# MOSFET.net
KiCad netlist of a schematic drawn in Altium Designer
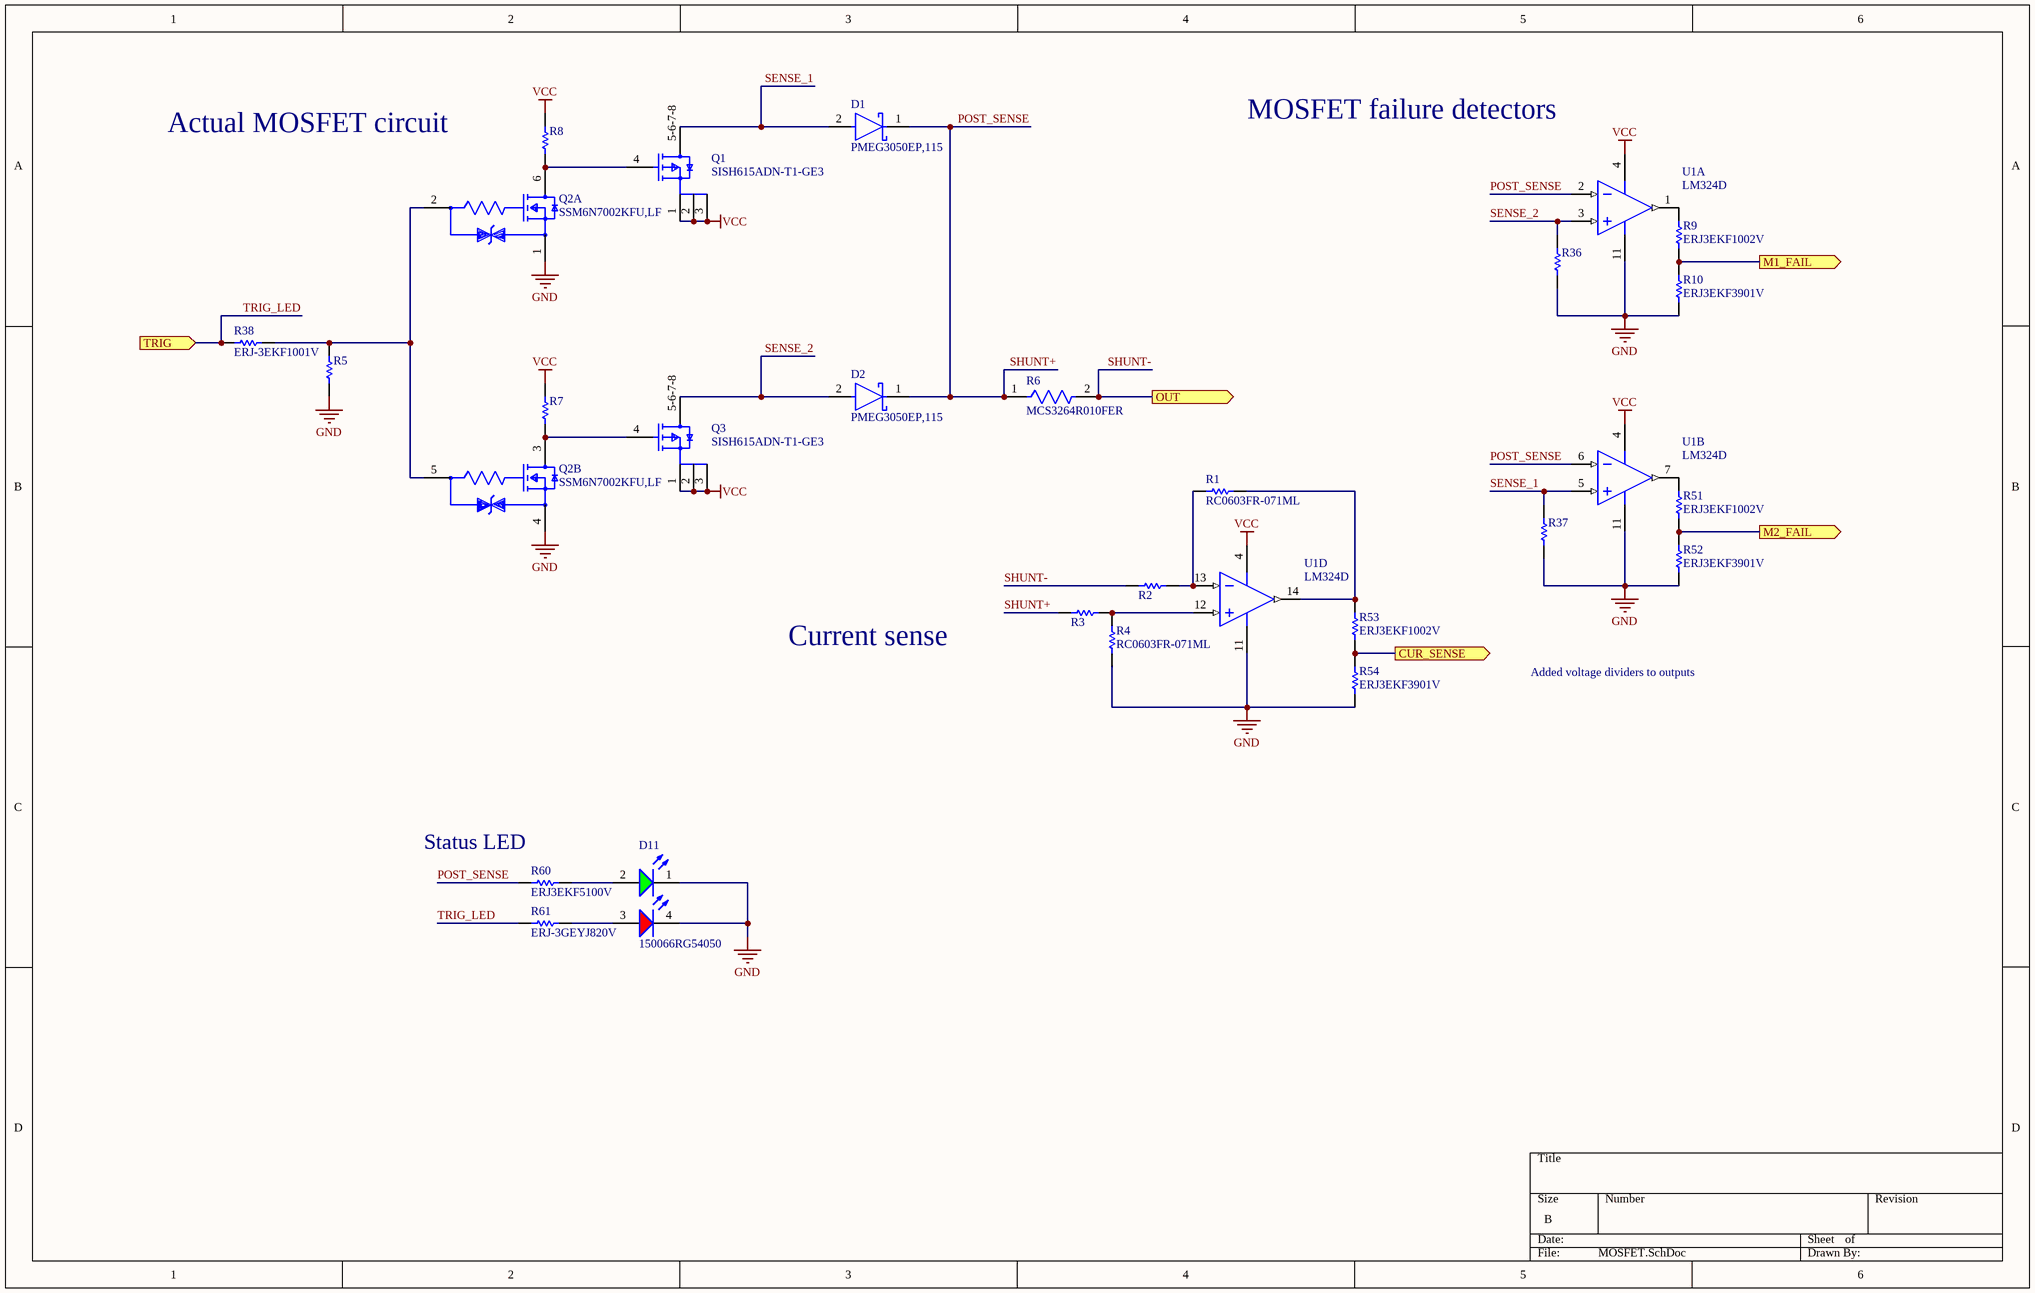
[diagram p0: MOSFET.SchDoc]

(export (version "E")
  (design (tool "Eeschema 10.0.6"))
  (components
    (comp (ref "D1")
      (value "PMEG3050EP,115")
      (footprint "FP-SOD128-MFG")
      (description "DIODE SCHOTTKY 30V 5A SOD128")
      (libsource (lib "Altium Content Vault") (part "1d6ec82d83fb6aee721767c19dac4b9"))
    )
    (comp (ref "D2")
      (value "PMEG3050EP,115")
      (footprint "FP-SOD128-MFG")
      (description "DIODE SCHOTTKY 30V 5A SOD128")
      (libsource (lib "Altium Content Vault") (part "1d6ec82d83fb6aee721767c19dac4b9"))
    )
    (comp (ref "D11")
      (value "150066RG54050")
      (footprint "WL-SBCD_0606")
      (description "Led, Red/Grn, 180Mcd/230Mcd, 624Nm/525Nm Rohs Compliant: Yes")
      (libsource (lib "uORocketry Hardware") (part "WL-SBCD_0606_Red & Green"))
    )
    (comp (ref "Q1")
      (value "SISH615ADN-T1-GE3")
      (footprint "SISH615ADN-T1-GE3-Footprint-1")
      (description "Trans MOSFET P-CH 20V 22.1A 8-Pin PowerPAK 1212 EP T/R")
      (libsource (lib "uORocketry Hardware") (part "SISH615ADN-T1-GE3-Symbol-1"))
    )
    (comp (ref "Q2")
      (value "SSM6N7002KFU,LF")
      (footprint "FP-SSOP6-P-0_65A-MFG")
      (description "MOSFET 2N-CH 60V 0.3A")
      (libsource (lib "Altium Content Vault") (part "088aa6ac103fdeebe0d1c52ece6b7b9"))
    )
    (comp (ref "Q3")
      (value "SISH615ADN-T1-GE3")
      (footprint "SISH615ADN-T1-GE3-Footprint-1")
      (description "Trans MOSFET P-CH 20V 22.1A 8-Pin PowerPAK 1212 EP T/R")
      (libsource (lib "uORocketry Hardware") (part "SISH615ADN-T1-GE3-Symbol-1"))
    )
    (comp (ref "R1")
      (value "RC0603FR-071ML")
      (footprint "RESC1608X55X25LL10T15")
      (description "Chip Resistor, 1 MOhm, +/- 1%, 100 mW, -55 to 155 degC, 0603 (1608 Metric), RoHS, Tape and Reel")
      (fields (field (name "TOLERANCE") "20%"))
      (libsource (lib "Altium Content Vault") (part "RES-2"))
    )
    (comp (ref "R2")
      (value "ERJ3EKF1002V")
      (footprint "RESC1609X55X30LL15T15")
      (description "Chip Resistor, 10 KOhm, +/- 1%, 0.1 W, -55 to 155 degC, 0603 (1608 Metric), RoHS, Tape and Reel")
      (fields (field (name "TOLERANCE") "1%") (field (name "MANUFACTURER") "Panasonic"))
      (libsource (lib "Altium Content Vault") (part "RES-2"))
    )
    (comp (ref "R3")
      (value "ERJ3EKF1002V")
      (footprint "RESC1609X55X30LL15T15")
      (description "Chip Resistor, 10 KOhm, +/- 1%, 0.1 W, -55 to 155 degC, 0603 (1608 Metric), RoHS, Tape and Reel")
      (fields (field (name "TOLERANCE") "1%") (field (name "MANUFACTURER") "Panasonic"))
      (libsource (lib "Altium Content Vault") (part "RES-2"))
    )
    (comp (ref "R4")
      (value "RC0603FR-071ML")
      (footprint "RESC1608X55X25LL10T15")
      (description "Chip Resistor, 1 MOhm, +/- 1%, 100 mW, -55 to 155 degC, 0603 (1608 Metric), RoHS, Tape and Reel")
      (fields (field (name "TOLERANCE") "20%"))
      (libsource (lib "Altium Content Vault") (part "RES-2"))
    )
    (comp (ref "R5")
      (value "ERJ3EKF1002V")
      (footprint "RESC1609X55X30LL15T15")
      (description "Chip Resistor, 10 KOhm, +/- 1%, 0.1 W, -55 to 155 degC, 0603 (1608 Metric), RoHS, Tape and Reel")
      (fields (field (name "TOLERANCE") "1%") (field (name "MANUFACTURER") "Panasonic"))
      (libsource (lib "Altium Content Vault") (part "RES-2"))
    )
    (comp (ref "R6")
      (value "MCS3264R010FER")
      (footprint "FP-MCS3264-MFG")
      (description "RES SMD 10 MOHM 1% 2W 3264")
      (fields (field (name "TOLERANCE") "1%"))
      (libsource (lib "Altium Content Vault") (part "1029c3af85768c4190bb7ad29bc67b5"))
    )
    (comp (ref "R7")
      (value "ERJ3EKF1002V")
      (footprint "RESC1609X55X30LL15T15")
      (description "Chip Resistor, 10 KOhm, +/- 1%, 0.1 W, -55 to 155 degC, 0603 (1608 Metric), RoHS, Tape and Reel")
      (fields (field (name "TOLERANCE") "1%") (field (name "MANUFACTURER") "Panasonic"))
      (libsource (lib "Altium Content Vault") (part "RES-2"))
    )
    (comp (ref "R8")
      (value "ERJ3EKF1002V")
      (footprint "RESC1609X55X30LL15T15")
      (description "Chip Resistor, 10 KOhm, +/- 1%, 0.1 W, -55 to 155 degC, 0603 (1608 Metric), RoHS, Tape and Reel")
      (fields (field (name "TOLERANCE") "1%") (field (name "MANUFACTURER") "Panasonic"))
      (libsource (lib "Altium Content Vault") (part "RES-2"))
    )
    (comp (ref "R9")
      (value "ERJ3EKF1002V")
      (footprint "RESC1609X55X30LL15T15")
      (description "Chip Resistor, 10 KOhm, +/- 1%, 0.1 W, -55 to 155 degC, 0603 (1608 Metric), RoHS, Tape and Reel")
      (fields (field (name "TOLERANCE") "1%") (field (name "MANUFACTURER") "Panasonic"))
      (libsource (lib "Altium Content Vault") (part "RES-2"))
    )
    (comp (ref "R10")
      (value "ERJ3EKF3901V")
      (footprint "RESC1608X55X30ML15T15")
      (fields (field (name "MANUFACTURER") "Panasonic"))
      (libsource (lib "Altium Content Vault") (part "RES"))
    )
    (comp (ref "R36")
      (value "ERJ-3EKF1003V")
      (footprint "RESC1608X55X30ML15T15")
      (fields (field (name "MANUFACTURER") "Panasonic"))
      (libsource (lib "Altium Content Vault") (part "RES"))
    )
    (comp (ref "R37")
      (value "ERJ-3EKF1003V")
      (footprint "RESC1608X55X30ML15T15")
      (fields (field (name "MANUFACTURER") "Panasonic"))
      (libsource (lib "Altium Content Vault") (part "RES"))
    )
    (comp (ref "R38")
      (value "ERJ-3EKF1001V")
      (footprint "RESC1608X55X30LL15T15")
      (fields (field (name "MANUFACTURER") "Panasonic"))
      (libsource (lib "Altium Content Vault") (part "RES"))
    )
    (comp (ref "R51")
      (value "ERJ3EKF1002V")
      (footprint "RESC1609X55X30LL15T15")
      (description "Chip Resistor, 10 KOhm, +/- 1%, 0.1 W, -55 to 155 degC, 0603 (1608 Metric), RoHS, Tape and Reel")
      (fields (field (name "TOLERANCE") "1%") (field (name "MANUFACTURER") "Panasonic"))
      (libsource (lib "Altium Content Vault") (part "RES-2"))
    )
    (comp (ref "R52")
      (value "ERJ3EKF3901V")
      (footprint "RESC1608X55X30ML15T15")
      (fields (field (name "MANUFACTURER") "Panasonic"))
      (libsource (lib "Altium Content Vault") (part "RES"))
    )
    (comp (ref "R53")
      (value "ERJ3EKF1002V")
      (footprint "RESC1609X55X30LL15T15")
      (description "Chip Resistor, 10 KOhm, +/- 1%, 0.1 W, -55 to 155 degC, 0603 (1608 Metric), RoHS, Tape and Reel")
      (fields (field (name "TOLERANCE") "1%") (field (name "MANUFACTURER") "Panasonic"))
      (libsource (lib "Altium Content Vault") (part "RES-2"))
    )
    (comp (ref "R54")
      (value "ERJ3EKF3901V")
      (footprint "RESC1608X55X30ML15T15")
      (fields (field (name "MANUFACTURER") "Panasonic"))
      (libsource (lib "Altium Content Vault") (part "RES"))
    )
    (comp (ref "R60")
      (value "ERJ3EKF5100V")
      (footprint "RESC1608X55X30NL15T15")
      (fields (field (name "MANUFACTURER") "Panasonic"))
      (libsource (lib "Altium Content Vault") (part "RES"))
    )
    (comp (ref "R61")
      (value "ERJ-3GEYJ820V")
      (footprint "RESC1608X55X30NL15T15")
      (fields (field (name "MANUFACTURER") "Panasonic"))
      (libsource (lib "Altium Content Vault") (part "RES"))
    )
    (comp (ref "U1")
      (value "LM324D")
      (footprint "D0014A_L")
      (fields (field (name "MANUFACTURER") "Texas Instruments"))
      (libsource (lib "Altium Content Vault") (part "TI-LMX24_2902X-X14"))
    )
  )
  (nets
    (net (code "1") (name "/CUR_SENSE") (class "Default")
      (node (ref "R53") (pin "1") (pinfunction "1_1") (pintype "passive"))
      (node (ref "R54") (pin "2") (pinfunction "2_2") (pintype "passive"))
    )
    (net (code "2") (name "/M1_FAIL") (class "Default")
      (node (ref "R10") (pin "2") (pinfunction "2_2") (pintype "passive"))
      (node (ref "R9") (pin "1") (pinfunction "1_1") (pintype "passive"))
    )
    (net (code "3") (name "/M2_FAIL") (class "Default")
      (node (ref "R51") (pin "1") (pinfunction "1_1") (pintype "passive"))
      (node (ref "R52") (pin "2") (pinfunction "2_2") (pintype "passive"))
    )
    (net (code "4") (name "/POST_SENSE") (class "Default")
      (node (ref "D1") (pin "1") (pinfunction "C_1") (pintype "passive"))
      (node (ref "D2") (pin "1") (pinfunction "C_1") (pintype "passive"))
      (node (ref "R3") (pin "2") (pinfunction "2_2") (pintype "passive"))
      (node (ref "R6") (pin "1") (pinfunction "1_1") (pintype "passive"))
      (node (ref "R60") (pin "1") (pinfunction "1_1") (pintype "passive"))
      (node (ref "U1") (pin "2") (pinfunction "1IN-_2") (pintype "input"))
      (node (ref "U1") (pin "6") (pinfunction "2IN-_6") (pintype "input"))
    )
    (net (code "5") (name "/SENSE_1") (class "Default")
      (node (ref "D1") (pin "2") (pinfunction "A_2") (pintype "passive"))
      (node (ref "Q1") (pin "5-6-7-8") (pinfunction "D_5-6-7-8") (pintype "passive"))
      (node (ref "R37") (pin "2") (pinfunction "2_2") (pintype "passive"))
      (node (ref "U1") (pin "5") (pinfunction "2IN+_5") (pintype "input"))
    )
    (net (code "6") (name "/SENSE_2") (class "Default")
      (node (ref "D2") (pin "2") (pinfunction "A_2") (pintype "passive"))
      (node (ref "Q3") (pin "5-6-7-8") (pinfunction "D_5-6-7-8") (pintype "passive"))
      (node (ref "R36") (pin "2") (pinfunction "2_2") (pintype "passive"))
      (node (ref "U1") (pin "3") (pinfunction "1IN+_3") (pintype "input"))
    )
    (net (code "7") (name "/SHUNT-") (class "Default")
      (node (ref "R2") (pin "2") (pinfunction "2_2") (pintype "passive"))
      (node (ref "R6") (pin "2") (pinfunction "2_2") (pintype "passive"))
    )
    (net (code "8") (name "/TRIG_LED") (class "Default")
      (node (ref "R38") (pin "1") (pinfunction "1_1") (pintype "passive"))
      (node (ref "R61") (pin "1") (pinfunction "1_1") (pintype "passive"))
    )
    (net (code "9") (name "GND") (class "Default")
      (node (ref "D11") (pin "1") (pinfunction "K_1") (pintype "passive"))
      (node (ref "D11") (pin "4") (pinfunction "K_4") (pintype "passive"))
      (node (ref "Q2") (pin "1") (pinfunction "Source1_1") (pintype "passive"))
      (node (ref "Q2") (pin "4") (pinfunction "Source2_4") (pintype "passive"))
      (node (ref "R10") (pin "1") (pinfunction "1_1") (pintype "passive"))
      (node (ref "R36") (pin "1") (pinfunction "1_1") (pintype "passive"))
      (node (ref "R37") (pin "1") (pinfunction "1_1") (pintype "passive"))
      (node (ref "R4") (pin "1") (pinfunction "1_1") (pintype "passive"))
      (node (ref "R5") (pin "1") (pinfunction "1_1") (pintype "passive"))
      (node (ref "R52") (pin "1") (pinfunction "1_1") (pintype "passive"))
      (node (ref "R54") (pin "1") (pinfunction "1_1") (pintype "passive"))
      (node (ref "U1") (pin "11") (pinfunction "GND_11") (pintype "power_in"))
    )
    (net (code "10") (name "Net-(D11-A-Pad2)") (class "Default")
      (node (ref "D11") (pin "2") (pinfunction "A_2") (pintype "passive"))
      (node (ref "R60") (pin "2") (pinfunction "2_2") (pintype "passive"))
    )
    (net (code "11") (name "Net-(D11-A-Pad3)") (class "Default")
      (node (ref "D11") (pin "3") (pinfunction "A_3") (pintype "passive"))
      (node (ref "R61") (pin "2") (pinfunction "2_2") (pintype "passive"))
    )
    (net (code "12") (name "Net-(Q1-G)") (class "Default")
      (node (ref "Q1") (pin "4") (pinfunction "G_4") (pintype "passive"))
      (node (ref "Q2") (pin "6") (pinfunction "Drain1_6") (pintype "passive"))
      (node (ref "R8") (pin "1") (pinfunction "1_1") (pintype "passive"))
    )
    (net (code "13") (name "Net-(Q2A-Gate1)") (class "Default")
      (node (ref "Q2") (pin "2") (pinfunction "Gate1_2") (pintype "passive"))
      (node (ref "Q2") (pin "5") (pinfunction "Gate2_5") (pintype "passive"))
      (node (ref "R38") (pin "2") (pinfunction "2_2") (pintype "passive"))
      (node (ref "R5") (pin "2") (pinfunction "2_2") (pintype "passive"))
    )
    (net (code "14") (name "Net-(Q2B-Drain2)") (class "Default")
      (node (ref "Q2") (pin "3") (pinfunction "Drain2_3") (pintype "passive"))
      (node (ref "Q3") (pin "4") (pinfunction "G_4") (pintype "passive"))
      (node (ref "R7") (pin "1") (pinfunction "1_1") (pintype "passive"))
    )
    (net (code "15") (name "Net-(U1A-1OUT)") (class "Default")
      (node (ref "R9") (pin "2") (pinfunction "2_2") (pintype "passive"))
      (node (ref "U1") (pin "1") (pinfunction "1OUT_1") (pintype "output"))
    )
    (net (code "16") (name "Net-(U1B-2OUT)") (class "Default")
      (node (ref "R51") (pin "2") (pinfunction "2_2") (pintype "passive"))
      (node (ref "U1") (pin "7") (pinfunction "2OUT_7") (pintype "output"))
    )
    (net (code "17") (name "Net-(U1D-4IN+)") (class "Default")
      (node (ref "R3") (pin "1") (pinfunction "1_1") (pintype "passive"))
      (node (ref "R4") (pin "2") (pinfunction "2_2") (pintype "passive"))
      (node (ref "U1") (pin "12") (pinfunction "4IN+_12") (pintype "input"))
    )
    (net (code "18") (name "Net-(U1D-4IN-)") (class "Default")
      (node (ref "R1") (pin "1") (pinfunction "1_1") (pintype "passive"))
      (node (ref "R2") (pin "1") (pinfunction "1_1") (pintype "passive"))
      (node (ref "U1") (pin "13") (pinfunction "4IN-_13") (pintype "input"))
    )
    (net (code "19") (name "Net-(U1D-4OUT)") (class "Default")
      (node (ref "R1") (pin "2") (pinfunction "2_2") (pintype "passive"))
      (node (ref "R53") (pin "2") (pinfunction "2_2") (pintype "passive"))
      (node (ref "U1") (pin "14") (pinfunction "4OUT_14") (pintype "output"))
    )
    (net (code "20") (name "VCC") (class "Default")
      (node (ref "Q1") (pin "1") (pinfunction "S_1") (pintype "passive"))
      (node (ref "Q1") (pin "2") (pinfunction "S_2") (pintype "passive"))
      (node (ref "Q1") (pin "3") (pinfunction "S_3") (pintype "passive"))
      (node (ref "Q3") (pin "1") (pinfunction "S_1") (pintype "passive"))
      (node (ref "Q3") (pin "2") (pinfunction "S_2") (pintype "passive"))
      (node (ref "Q3") (pin "3") (pinfunction "S_3") (pintype "passive"))
      (node (ref "R7") (pin "2") (pinfunction "2_2") (pintype "passive"))
      (node (ref "R8") (pin "2") (pinfunction "2_2") (pintype "passive"))
      (node (ref "U1") (pin "4") (pinfunction "VCC_4") (pintype "power_in"))
    )
  )
)
